# dwm1000.net
KiCad netlist of a schematic drawn in EAGLE
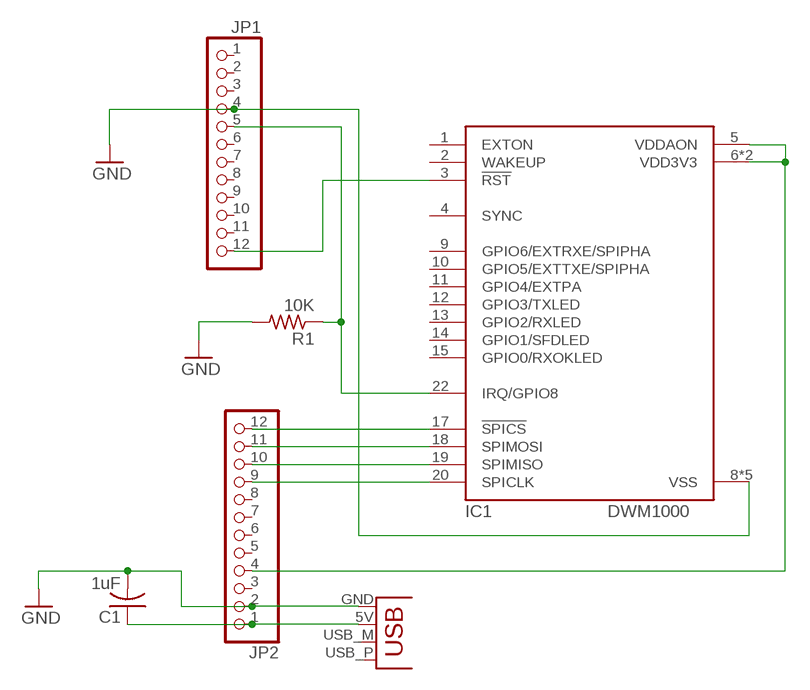
[diagram p0: schematic, sheet 1]

(export (version "E")
  (design (tool "Eeschema 10.0.6"))
  (components
    (comp (ref "C1")
      (value "1uF")
      (footprint "eagle-import:C025-024X044")
      (libsource (lib "eagle-import") (part "C-US025-024X044"))
    )
    (comp (ref "IC1")
      (value "DWM1000")
      (footprint "eagle-import:DWM1000")
      (libsource (lib "eagle-import") (part "DWM1000"))
    )
    (comp (ref "JP1")
      (value "PINHD-1X12")
      (footprint "eagle-import:1X12")
      (libsource (lib "eagle-import") (part "PINHD-1X12"))
    )
    (comp (ref "JP2")
      (value "PINHD-1X12")
      (footprint "eagle-import:1X12")
      (libsource (lib "eagle-import") (part "PINHD-1X12"))
    )
    (comp (ref "JP3")
      (value "USBPCB")
      (footprint "eagle-import:USB-A-PCB")
      (libsource (lib "eagle-import") (part "USBPCB"))
    )
    (comp (ref "R1")
      (value "10K")
      (footprint "eagle-import:0207_7")
      (libsource (lib "eagle-import") (part "R-US_0207/7"))
    )
  )
  (nets
    (net (code "1") (name "GND") (class "Default")
      (node (ref "C1") (pin "2") (pinfunction "2_2") (pintype "passive"))
      (node (ref "IC1") (pin "16") (pinfunction "VSS_16") (pintype "bidirectional"))
      (node (ref "IC1") (pin "21") (pinfunction "VSS_21") (pintype "bidirectional"))
      (node (ref "IC1") (pin "23") (pinfunction "VSS_23") (pintype "bidirectional"))
      (node (ref "IC1") (pin "24") (pinfunction "VSS_24") (pintype "bidirectional"))
      (node (ref "IC1") (pin "8") (pinfunction "VSS_8") (pintype "bidirectional"))
      (node (ref "JP1") (pin "4") (pinfunction "4_4") (pintype "passive"))
      (node (ref "JP2") (pin "2") (pinfunction "2_2") (pintype "passive"))
      (node (ref "JP3") (pin "GND") (pinfunction "GND_GND") (pintype "bidirectional"))
      (node (ref "R1") (pin "2") (pinfunction "2_2") (pintype "passive"))
    )
    (net (code "2") (name "Net-(IC1-IRQ{slash}GPIO8)") (class "Default")
      (node (ref "IC1") (pin "22") (pinfunction "IRQ/GPIO8_22") (pintype "bidirectional"))
      (node (ref "JP1") (pin "5") (pinfunction "5_5") (pintype "passive"))
      (node (ref "R1") (pin "1") (pinfunction "1_1") (pintype "passive"))
    )
    (net (code "3") (name "Net-(IC1-SPICLK)") (class "Default")
      (node (ref "IC1") (pin "20") (pinfunction "SPICLK_20") (pintype "bidirectional"))
      (node (ref "JP2") (pin "9") (pinfunction "9_9") (pintype "passive"))
    )
    (net (code "4") (name "Net-(IC1-SPIMISO)") (class "Default")
      (node (ref "IC1") (pin "19") (pinfunction "SPIMISO_19") (pintype "bidirectional"))
      (node (ref "JP2") (pin "10") (pinfunction "10_10") (pintype "passive"))
    )
    (net (code "5") (name "Net-(IC1-SPIMOSI)") (class "Default")
      (node (ref "IC1") (pin "18") (pinfunction "SPIMOSI_18") (pintype "bidirectional"))
      (node (ref "JP2") (pin "11") (pinfunction "11_11") (pintype "passive"))
    )
    (net (code "6") (name "Net-(IC1-VDDAON)") (class "Default")
      (node (ref "IC1") (pin "5") (pinfunction "VDDAON_5") (pintype "bidirectional"))
      (node (ref "IC1") (pin "6") (pinfunction "VDD3V3_6") (pintype "bidirectional"))
      (node (ref "IC1") (pin "7") (pinfunction "VDD3V3_7") (pintype "bidirectional"))
      (node (ref "JP2") (pin "4") (pinfunction "4_4") (pintype "passive"))
    )
    (net (code "7") (name "Net-(IC1-~{RST})") (class "Default")
      (node (ref "IC1") (pin "3") (pinfunction "~{RST}_3") (pintype "bidirectional"))
      (node (ref "JP1") (pin "12") (pinfunction "12_12") (pintype "passive"))
    )
    (net (code "8") (name "Net-(IC1-~{SPICS})") (class "Default")
      (node (ref "IC1") (pin "17") (pinfunction "~{SPICS}_17") (pintype "bidirectional"))
      (node (ref "JP2") (pin "12") (pinfunction "12_12") (pintype "passive"))
    )
    (net (code "9") (name "Net-(JP3-VBUS)") (class "Default")
      (node (ref "C1") (pin "1") (pinfunction "1_1") (pintype "passive"))
      (node (ref "JP2") (pin "1") (pinfunction "1_1") (pintype "passive"))
      (node (ref "JP3") (pin "5V") (pinfunction "VBUS_5V") (pintype "bidirectional"))
    )
    (net (code "10") (name "unconnected-(IC1-EXTON-Pad1)") (class "Default")
      (node (ref "IC1") (pin "1") (pinfunction "EXTON_1") (pintype "bidirectional"))
    )
    (net (code "11") (name "unconnected-(IC1-GPIO0{slash}RXOKLED-Pad15)") (class "Default")
      (node (ref "IC1") (pin "15") (pinfunction "GPIO0/RXOKLED_15") (pintype "bidirectional"))
    )
    (net (code "12") (name "unconnected-(IC1-GPIO1{slash}SFDLED-Pad14)") (class "Default")
      (node (ref "IC1") (pin "14") (pinfunction "GPIO1/SFDLED_14") (pintype "bidirectional"))
    )
    (net (code "13") (name "unconnected-(IC1-GPIO2{slash}RXLED-Pad13)") (class "Default")
      (node (ref "IC1") (pin "13") (pinfunction "GPIO2/RXLED_13") (pintype "bidirectional"))
    )
    (net (code "14") (name "unconnected-(IC1-GPIO3{slash}TXLED-Pad12)") (class "Default")
      (node (ref "IC1") (pin "12") (pinfunction "GPIO3/TXLED_12") (pintype "bidirectional"))
    )
    (net (code "15") (name "unconnected-(IC1-GPIO4{slash}EXTPA-Pad11)") (class "Default")
      (node (ref "IC1") (pin "11") (pinfunction "GPIO4/EXTPA_11") (pintype "bidirectional"))
    )
    (net (code "16") (name "unconnected-(IC1-GPIO5{slash}EXTTXE{slash}SPIPHA-Pad10)") (class "Default")
      (node (ref "IC1") (pin "10") (pinfunction "GPIO5/EXTTXE/SPIPHA_10") (pintype "bidirectional"))
    )
    (net (code "17") (name "unconnected-(IC1-GPIO6{slash}EXTRXE{slash}SPIPHA-Pad9)") (class "Default")
      (node (ref "IC1") (pin "9") (pinfunction "GPIO6/EXTRXE/SPIPHA_9") (pintype "bidirectional"))
    )
    (net (code "18") (name "unconnected-(IC1-SYNC-Pad4)") (class "Default")
      (node (ref "IC1") (pin "4") (pinfunction "SYNC_4") (pintype "bidirectional"))
    )
    (net (code "19") (name "unconnected-(IC1-WAKEUP-Pad2)") (class "Default")
      (node (ref "IC1") (pin "2") (pinfunction "WAKEUP_2") (pintype "bidirectional"))
    )
    (net (code "20") (name "unconnected-(JP1-Pad1)") (class "Default")
      (node (ref "JP1") (pin "1") (pinfunction "1_1") (pintype "passive"))
    )
    (net (code "21") (name "unconnected-(JP1-Pad2)") (class "Default")
      (node (ref "JP1") (pin "2") (pinfunction "2_2") (pintype "passive"))
    )
    (net (code "22") (name "unconnected-(JP1-Pad3)") (class "Default")
      (node (ref "JP1") (pin "3") (pinfunction "3_3") (pintype "passive"))
    )
    (net (code "23") (name "unconnected-(JP1-Pad6)") (class "Default")
      (node (ref "JP1") (pin "6") (pinfunction "6_6") (pintype "passive"))
    )
    (net (code "24") (name "unconnected-(JP1-Pad7)") (class "Default")
      (node (ref "JP1") (pin "7") (pinfunction "7_7") (pintype "passive"))
    )
    (net (code "25") (name "unconnected-(JP1-Pad8)") (class "Default")
      (node (ref "JP1") (pin "8") (pinfunction "8_8") (pintype "passive"))
    )
    (net (code "26") (name "unconnected-(JP1-Pad9)") (class "Default")
      (node (ref "JP1") (pin "9") (pinfunction "9_9") (pintype "passive"))
    )
    (net (code "27") (name "unconnected-(JP1-Pad10)") (class "Default")
      (node (ref "JP1") (pin "10") (pinfunction "10_10") (pintype "passive"))
    )
    (net (code "28") (name "unconnected-(JP1-Pad11)") (class "Default")
      (node (ref "JP1") (pin "11") (pinfunction "11_11") (pintype "passive"))
    )
    (net (code "29") (name "unconnected-(JP2-Pad3)") (class "Default")
      (node (ref "JP2") (pin "3") (pinfunction "3_3") (pintype "passive"))
    )
    (net (code "30") (name "unconnected-(JP2-Pad5)") (class "Default")
      (node (ref "JP2") (pin "5") (pinfunction "5_5") (pintype "passive"))
    )
    (net (code "31") (name "unconnected-(JP2-Pad6)") (class "Default")
      (node (ref "JP2") (pin "6") (pinfunction "6_6") (pintype "passive"))
    )
    (net (code "32") (name "unconnected-(JP2-Pad7)") (class "Default")
      (node (ref "JP2") (pin "7") (pinfunction "7_7") (pintype "passive"))
    )
    (net (code "33") (name "unconnected-(JP2-Pad8)") (class "Default")
      (node (ref "JP2") (pin "8") (pinfunction "8_8") (pintype "passive"))
    )
    (net (code "34") (name "unconnected-(JP3-D+-PadUSB_P)") (class "Default")
      (node (ref "JP3") (pin "USB_P") (pinfunction "D+_USB_P") (pintype "bidirectional"))
    )
    (net (code "35") (name "unconnected-(JP3-D--PadUSB_M)") (class "Default")
      (node (ref "JP3") (pin "USB_M") (pinfunction "D-_USB_M") (pintype "bidirectional"))
    )
  )
)
